# ats_relay.net
KiCad netlist of a schematic drawn in Altium Designer
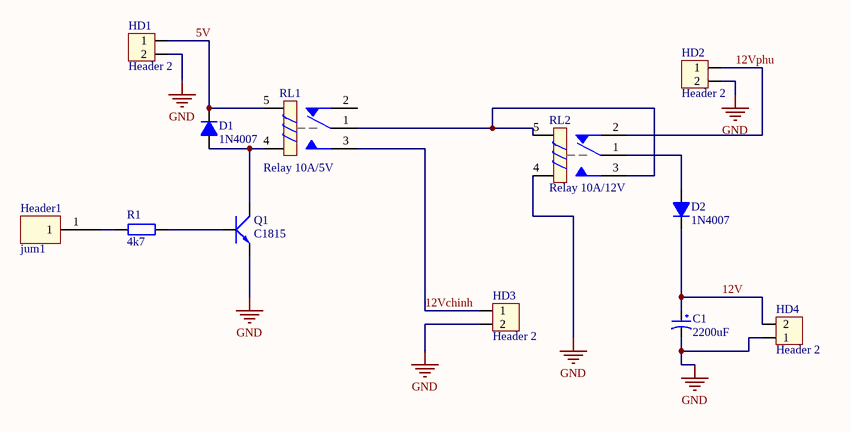
[diagram p0: ats_relay.SchDoc]

(export (version "E")
  (design (tool "Eeschema 10.0.6"))
  (components
    (comp (ref "C1")
      (value "2200uF")
      (footprint "CP1/2")
      (description "Cap P  0,1uF < 22uF , 16 - 50V")
      (libsource (lib "syhaunguyen") (part "CP1"))
    )
    (comp (ref "D1")
      (value "1N4007")
      (footprint "D1A")
      (description "Diode 1A")
      (libsource (lib "syhaunguyen") (part "D1A"))
    )
    (comp (ref "D2")
      (value "1N4007")
      (footprint "D1A")
      (description "Diode 1A")
      (libsource (lib "syhaunguyen") (part "D1A"))
    )
    (comp (ref "HD1")
      (value "Header 2")
      (footprint "HED2")
      (description "Header 2 (Green)")
      (libsource (lib "syhaunguyen") (part "Hed2"))
    )
    (comp (ref "HD2")
      (value "Header 2")
      (footprint "HED2")
      (description "Header 2 (Green)")
      (libsource (lib "syhaunguyen") (part "Hed2"))
    )
    (comp (ref "HD3")
      (value "Header 2")
      (footprint "HED2")
      (description "Header 2 (Green)")
      (libsource (lib "") (part "Hed2_1"))
    )
    (comp (ref "HD4")
      (value "Header 2")
      (footprint "HED2")
      (description "Header 2 (Green)")
      (libsource (lib "") (part "Hed2_2"))
    )
    (comp (ref "Header1") (value "jum1") (footprint "PCBComponent_1") (libsource (lib "jum1") (part "jum1")))
    (comp (ref "Q1")
      (value "C1815")
      (footprint "QTO-92")
      (description "NPN 600mW, ECB")
      (libsource (lib "syhaunguyen") (part "C1815"))
    )
    (comp (ref "R1")
      (value "4k7")
      (footprint "R1/4W")
      (description "Resistor 1/4W")
      (libsource (lib "syhaunguyen") (part "R1/4W"))
    )
    (comp (ref "RL1")
      (value "Relay 10A/5V")
      (footprint "RL_SPDT_10A")
      (description "Relay SPDT,10A - 12VDC 5 Pin")
      (libsource (lib "syhaunguyen") (part "Relay 1"))
    )
    (comp (ref "RL2")
      (value "Relay 10A/12V")
      (footprint "RL_SPDT_10A")
      (description "Relay SPDT,10A - 12VDC 5 Pin")
      (libsource (lib "syhaunguyen") (part "Relay 1"))
    )
  )
  (nets
    (net (code "1") (name "/5V") (class "Default")
      (node (ref "D1") (pin "2") (pinfunction "K_2") (pintype "passive"))
      (node (ref "HD1") (pin "1") (pinfunction "1_1") (pintype "passive"))
      (node (ref "RL1") (pin "5") (pinfunction "5_5") (pintype "passive"))
    )
    (net (code "2") (name "/12V") (class "Default")
      (node (ref "C1") (pin "1") (pinfunction "1_1") (pintype "passive"))
      (node (ref "D2") (pin "2") (pinfunction "K_2") (pintype "passive"))
      (node (ref "HD4") (pin "2") (pinfunction "2_2") (pintype "passive"))
    )
    (net (code "3") (name "/12Vchinh") (class "Default")
      (node (ref "HD3") (pin "1") (pinfunction "1_1") (pintype "passive"))
      (node (ref "RL1") (pin "3") (pinfunction "3_3") (pintype "passive"))
    )
    (net (code "4") (name "/12Vphu") (class "Default")
      (node (ref "HD2") (pin "1") (pinfunction "1_1") (pintype "passive"))
      (node (ref "RL2") (pin "2") (pinfunction "2_2") (pintype "passive"))
    )
    (net (code "5") (name "GND") (class "Default")
      (node (ref "C1") (pin "2") (pinfunction "2_2") (pintype "passive"))
      (node (ref "HD1") (pin "2") (pinfunction "2_2") (pintype "passive"))
      (node (ref "HD2") (pin "2") (pinfunction "2_2") (pintype "passive"))
      (node (ref "HD3") (pin "2") (pinfunction "2_2") (pintype "passive"))
      (node (ref "HD4") (pin "1") (pinfunction "1_1") (pintype "passive"))
      (node (ref "Q1") (pin "1") (pinfunction "E_1") (pintype "passive"))
      (node (ref "RL2") (pin "4") (pinfunction "4_4") (pintype "passive"))
    )
    (net (code "6") (name "Net-(D1-A)") (class "Default")
      (node (ref "D1") (pin "1") (pinfunction "A_1") (pintype "passive"))
      (node (ref "Q1") (pin "2") (pinfunction "C_2") (pintype "passive"))
      (node (ref "RL1") (pin "4") (pinfunction "4_4") (pintype "passive"))
    )
    (net (code "7") (name "Net-(D2-A)") (class "Default")
      (node (ref "D2") (pin "1") (pinfunction "A_1") (pintype "passive"))
      (node (ref "RL2") (pin "1") (pinfunction "1_1") (pintype "passive"))
    )
    (net (code "8") (name "Net-(Header1-Pad1)") (class "Default")
      (node (ref "Header1") (pin "1") (pinfunction "1_1") (pintype "passive"))
      (node (ref "R1") (pin "1") (pinfunction "1_1") (pintype "passive"))
    )
    (net (code "9") (name "Net-(Q1-B)") (class "Default")
      (node (ref "Q1") (pin "3") (pinfunction "B_3") (pintype "passive"))
      (node (ref "R1") (pin "2") (pinfunction "2_2") (pintype "passive"))
    )
    (net (code "10") (name "Net-(RL1-Pad1)") (class "Default")
      (node (ref "RL1") (pin "1") (pinfunction "1_1") (pintype "passive"))
      (node (ref "RL2") (pin "3") (pinfunction "3_3") (pintype "passive"))
      (node (ref "RL2") (pin "5") (pinfunction "5_5") (pintype "passive"))
    )
    (net (code "11") (name "unconnected-(RL1-Pad2)") (class "Default")
      (node (ref "RL1") (pin "2") (pinfunction "2_2") (pintype "passive"))
    )
  )
)
